# Vehicle_Accident_Detection.net
KiCad netlist of a schematic drawn in EasyEDA
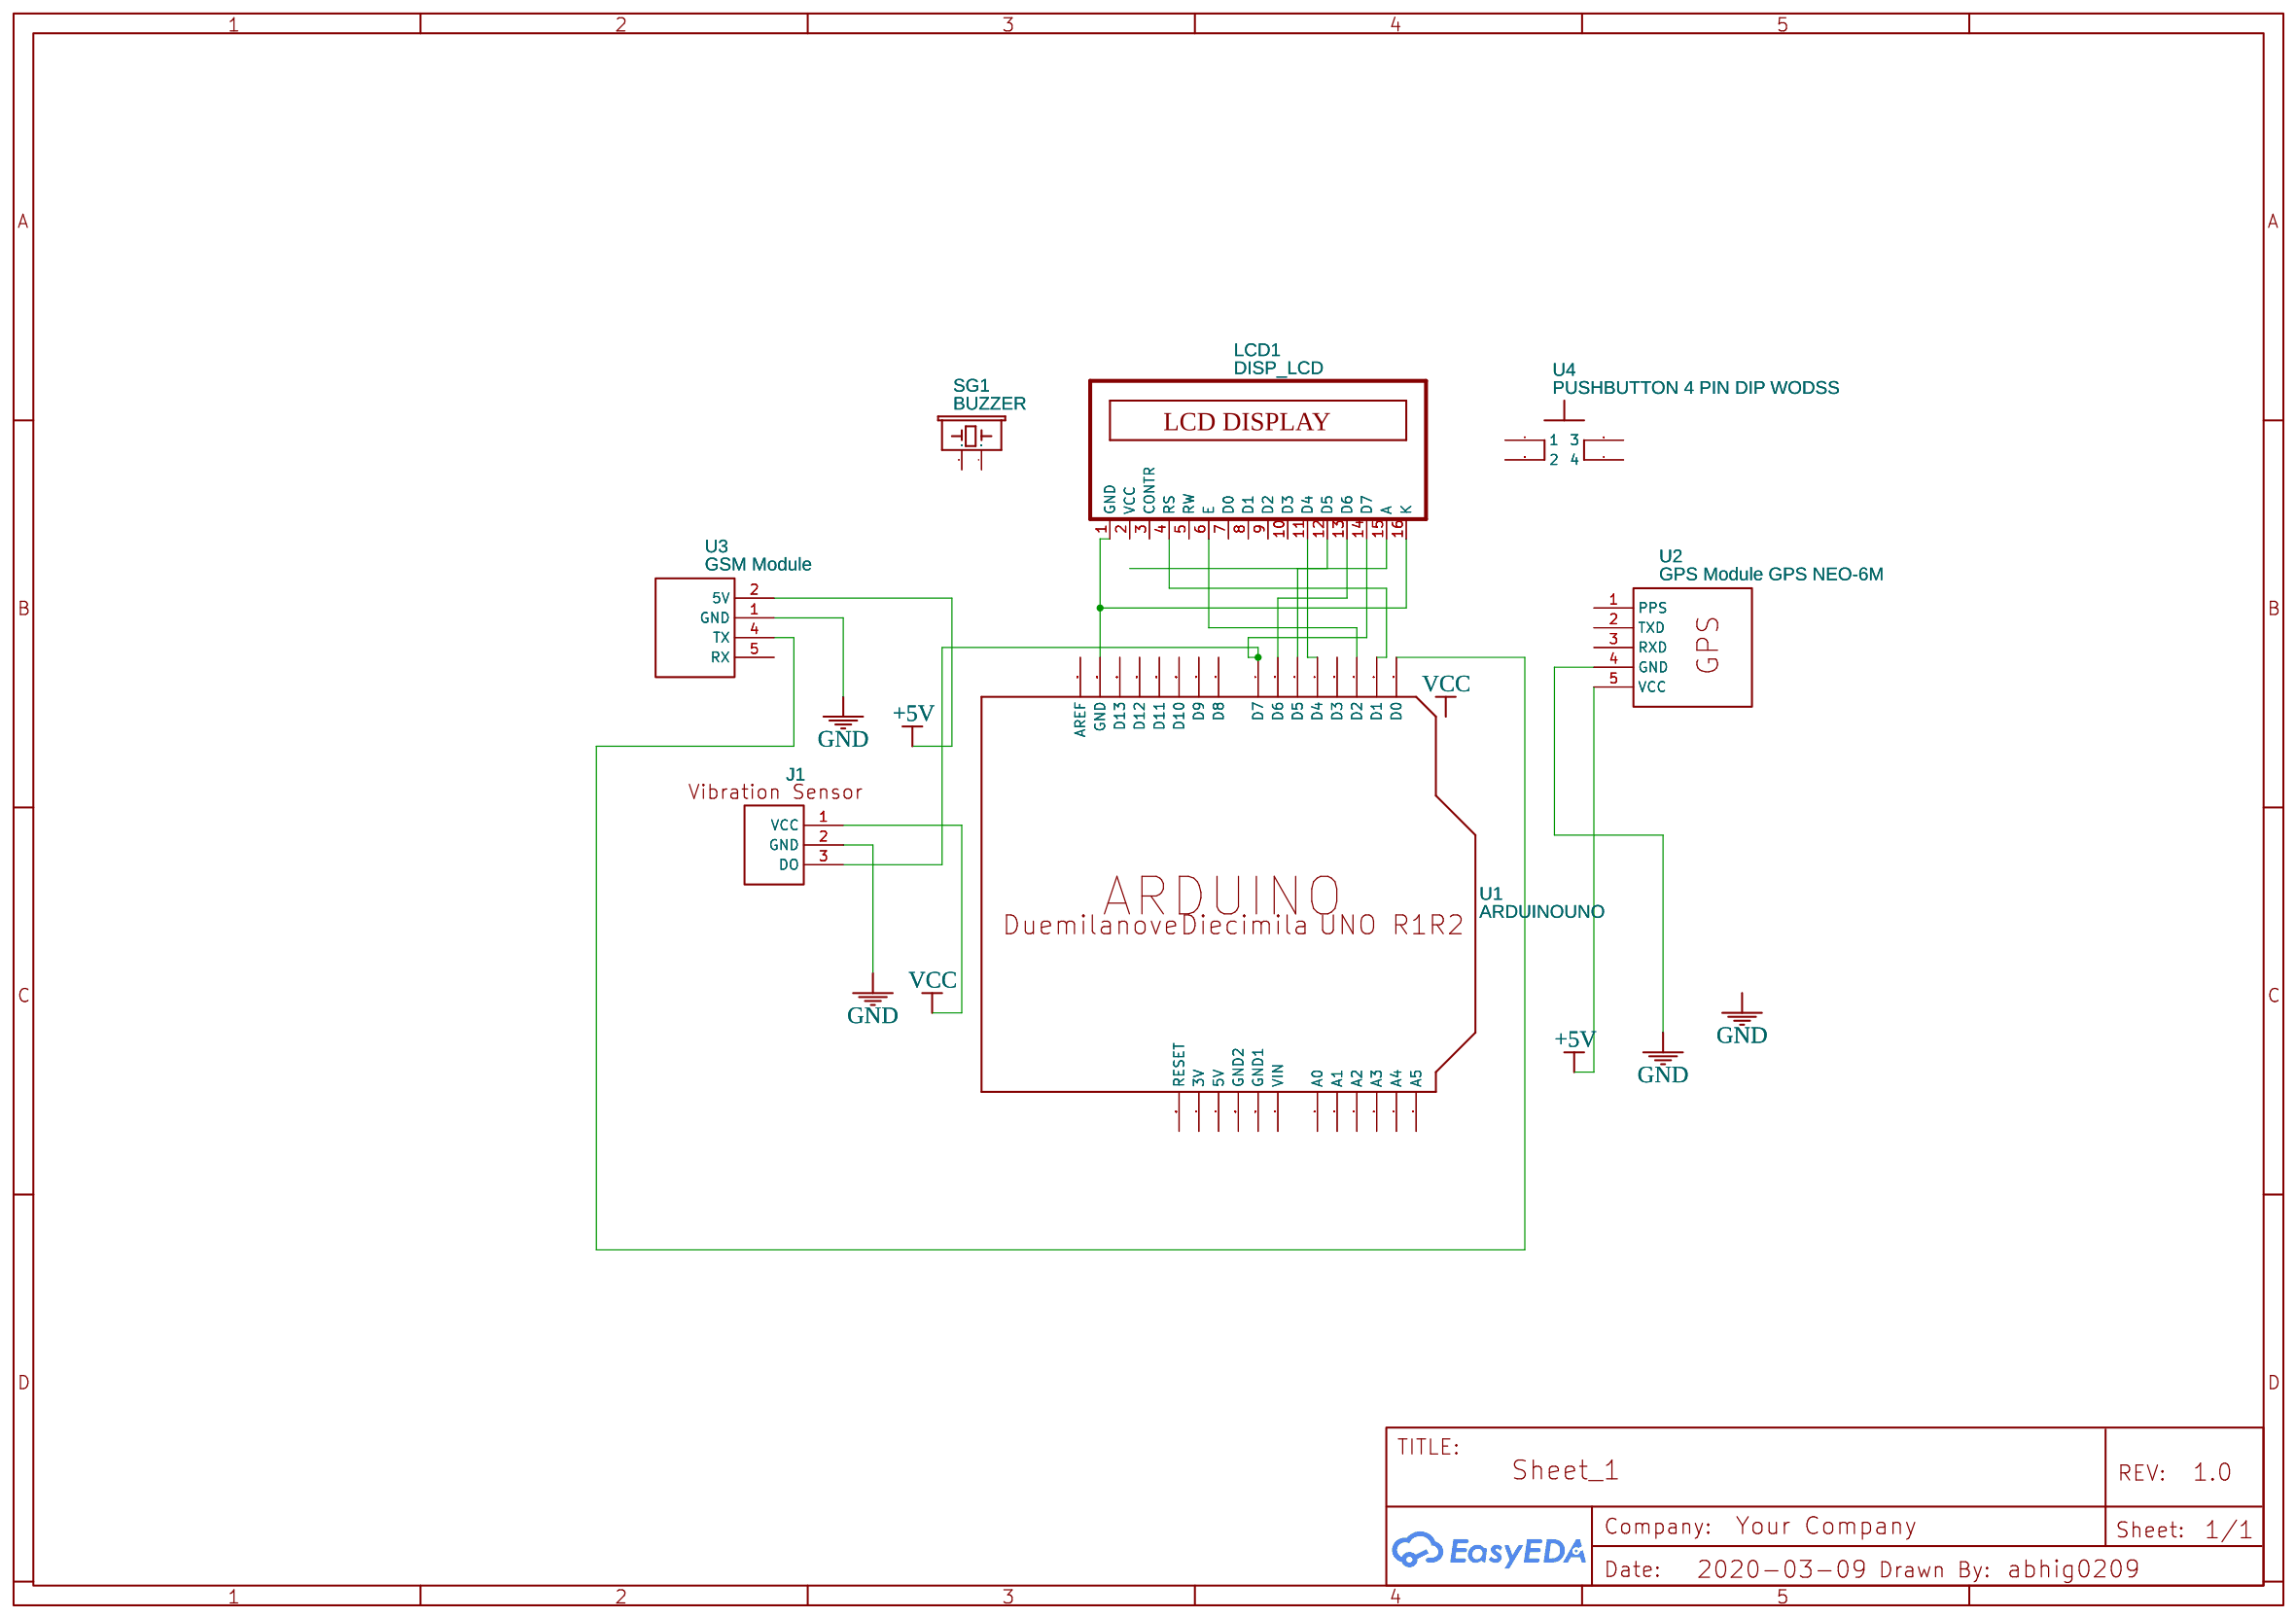
[diagram p0: schematic sheet]

(export (version "E")
  (design (tool "Eeschema 10.0.6"))
  (components
    (comp (ref "J1")
      (value "Vibration_Sensor")
      (fields (field (name "BOM_Manufacturer Part") "Vibration Sensor"))
      (libsource (lib "") (part "Vibration_Sensor"))
    )
    (comp (ref "LCD1") (value "DISP_LCD") (libsource (lib "") (part "DISP_LCD")))
    (comp (ref "SG1") (value "BUZZER") (libsource (lib "") (part "BUZZER")))
    (comp (ref "U1") (value "ARDUINOUNO") (libsource (lib "") (part "ARDUINOUNO")))
    (comp (ref "U2") (value "GPS Module GPS NEO-6M") (libsource (lib "") (part "GPS Module GPS NEO-6M")))
    (comp (ref "U3") (value "GSM Module") (libsource (lib "") (part "GSM Module")))
    (comp (ref "U4")
      (value "PUSHBUTTON 4 PIN DIP WODSS")
      (fields (field (name "BOM_Manufacturer Part") "Pushbutton"))
      (libsource (lib "") (part "PUSHBUTTON 4 PIN DIP WODSS"))
    )
  )
  (nets
    (net (code "1") (name "+5V") (class "Default")
      (node (ref "U2") (pin "5") (pinfunction "VCC_5") (pintype "unspecified"))
      (node (ref "U3") (pin "2") (pinfunction "5V_2") (pintype "unspecified"))
    )
    (net (code "2") (name "GND") (class "Default")
      (node (ref "J1") (pin "2") (pinfunction "GND_2") (pintype "unspecified"))
      (node (ref "U2") (pin "4") (pinfunction "GND_4") (pintype "unspecified"))
      (node (ref "U3") (pin "1") (pinfunction "GND_1") (pintype "unspecified"))
    )
    (net (code "3") (name "Net-(J1-DO)") (class "Default")
      (node (ref "J1") (pin "3") (pinfunction "DO_3") (pintype "unspecified"))
      (node (ref "LCD1") (pin "14") (pinfunction "D7_14") (pintype "input"))
      (node (ref "U1") (pin "D7") (pinfunction "D7_D7") (pintype "unspecified"))
    )
    (net (code "4") (name "Net-(LCD1-D4)") (class "Default")
      (node (ref "LCD1") (pin "11") (pinfunction "D4_11") (pintype "input"))
      (node (ref "U1") (pin "D4") (pinfunction "D4_D4") (pintype "unspecified"))
    )
    (net (code "5") (name "Net-(LCD1-D5)") (class "Default")
      (node (ref "LCD1") (pin "12") (pinfunction "D5_12") (pintype "input"))
      (node (ref "U1") (pin "D5") (pinfunction "D5_D5") (pintype "unspecified"))
    )
    (net (code "6") (name "Net-(LCD1-D6)") (class "Default")
      (node (ref "LCD1") (pin "13") (pinfunction "D6_13") (pintype "input"))
      (node (ref "U1") (pin "D6") (pinfunction "D6_D6") (pintype "unspecified"))
    )
    (net (code "7") (name "Net-(LCD1-E)") (class "Default")
      (node (ref "LCD1") (pin "6") (pinfunction "E_6") (pintype "input"))
      (node (ref "U1") (pin "D2") (pinfunction "D2_D2") (pintype "unspecified"))
    )
    (net (code "8") (name "Net-(LCD1-GND)") (class "Default")
      (node (ref "LCD1") (pin "1") (pinfunction "GND_1") (pintype "unspecified"))
      (node (ref "LCD1") (pin "16") (pinfunction "K_16") (pintype "unspecified"))
      (node (ref "U1") (pin "GND") (pinfunction "GND_GND") (pintype "passive"))
    )
    (net (code "9") (name "Net-(LCD1-RS)") (class "Default")
      (node (ref "LCD1") (pin "4") (pinfunction "RS_4") (pintype "input"))
      (node (ref "U1") (pin "D1") (pinfunction "D1_D1") (pintype "unspecified"))
    )
    (net (code "10") (name "Net-(U3-TX)") (class "Default")
      (node (ref "U1") (pin "D0") (pinfunction "D0_D0") (pintype "unspecified"))
      (node (ref "U3") (pin "4") (pinfunction "TX_4") (pintype "unspecified"))
    )
    (net (code "11") (name "VCC") (class "Default")
      (node (ref "J1") (pin "1") (pinfunction "VCC_1") (pintype "unspecified"))
    )
    (net (code "12") (name "unconnected-(LCD1-A-Pad15)") (class "Default")
      (node (ref "LCD1") (pin "15") (pinfunction "A_15") (pintype "unspecified"))
    )
    (net (code "13") (name "unconnected-(LCD1-CONTR-Pad3)") (class "Default")
      (node (ref "LCD1") (pin "3") (pinfunction "CONTR_3") (pintype "input"))
    )
    (net (code "14") (name "unconnected-(LCD1-D0-Pad7)") (class "Default")
      (node (ref "LCD1") (pin "7") (pinfunction "D0_7") (pintype "input"))
    )
    (net (code "15") (name "unconnected-(LCD1-D1-Pad8)") (class "Default")
      (node (ref "LCD1") (pin "8") (pinfunction "D1_8") (pintype "input"))
    )
    (net (code "16") (name "unconnected-(LCD1-D2-Pad9)") (class "Default")
      (node (ref "LCD1") (pin "9") (pinfunction "D2_9") (pintype "input"))
    )
    (net (code "17") (name "unconnected-(LCD1-D3-Pad10)") (class "Default")
      (node (ref "LCD1") (pin "10") (pinfunction "D3_10") (pintype "input"))
    )
    (net (code "18") (name "unconnected-(LCD1-RW-Pad5)") (class "Default")
      (node (ref "LCD1") (pin "5") (pinfunction "RW_5") (pintype "input"))
    )
    (net (code "19") (name "unconnected-(LCD1-VCC-Pad2)") (class "Default")
      (node (ref "LCD1") (pin "2") (pinfunction "VCC_2") (pintype "unspecified"))
    )
    (net (code "20") (name "unconnected-(SG1-1-Pad+)") (class "Default")
      (node (ref "SG1") (pin "+") (pinfunction "1_+") (pintype "unspecified"))
    )
    (net (code "21") (name "unconnected-(SG1-2-Pad-)") (class "Default")
      (node (ref "SG1") (pin "-") (pinfunction "2_-") (pintype "unspecified"))
    )
    (net (code "22") (name "unconnected-(U1-Pad3V)") (class "Default")
      (node (ref "U1") (pin "3V") (pinfunction "3V_3V") (pintype "passive"))
    )
    (net (code "23") (name "unconnected-(U1-Pad5V)") (class "Default")
      (node (ref "U1") (pin "5V") (pinfunction "5V_5V") (pintype "passive"))
    )
    (net (code "24") (name "unconnected-(U1-PadA0)") (class "Default")
      (node (ref "U1") (pin "A0") (pinfunction "A0_A0") (pintype "unspecified"))
    )
    (net (code "25") (name "unconnected-(U1-PadA1)") (class "Default")
      (node (ref "U1") (pin "A1") (pinfunction "A1_A1") (pintype "unspecified"))
    )
    (net (code "26") (name "unconnected-(U1-PadA2)") (class "Default")
      (node (ref "U1") (pin "A2") (pinfunction "A2_A2") (pintype "unspecified"))
    )
    (net (code "27") (name "unconnected-(U1-PadA3)") (class "Default")
      (node (ref "U1") (pin "A3") (pinfunction "A3_A3") (pintype "unspecified"))
    )
    (net (code "28") (name "unconnected-(U1-PadA4)") (class "Default")
      (node (ref "U1") (pin "A4") (pinfunction "A4_A4") (pintype "unspecified"))
    )
    (net (code "29") (name "unconnected-(U1-PadA5)") (class "Default")
      (node (ref "U1") (pin "A5") (pinfunction "A5_A5") (pintype "unspecified"))
    )
    (net (code "30") (name "unconnected-(U1-PadAREF)") (class "Default")
      (node (ref "U1") (pin "AREF") (pinfunction "AREF_AREF") (pintype "unspecified"))
    )
    (net (code "31") (name "unconnected-(U1-PadD3)") (class "Default")
      (node (ref "U1") (pin "D3") (pinfunction "D3_D3") (pintype "unspecified"))
    )
    (net (code "32") (name "unconnected-(U1-PadD8)") (class "Default")
      (node (ref "U1") (pin "D8") (pinfunction "D8_D8") (pintype "unspecified"))
    )
    (net (code "33") (name "unconnected-(U1-PadD9)") (class "Default")
      (node (ref "U1") (pin "D9") (pinfunction "D9_D9") (pintype "unspecified"))
    )
    (net (code "34") (name "unconnected-(U1-PadD10)") (class "Default")
      (node (ref "U1") (pin "D10") (pinfunction "D10_D10") (pintype "unspecified"))
    )
    (net (code "35") (name "unconnected-(U1-PadD11)") (class "Default")
      (node (ref "U1") (pin "D11") (pinfunction "D11_D11") (pintype "unspecified"))
    )
    (net (code "36") (name "unconnected-(U1-PadD12)") (class "Default")
      (node (ref "U1") (pin "D12") (pinfunction "D12_D12") (pintype "unspecified"))
    )
    (net (code "37") (name "unconnected-(U1-PadD13)") (class "Default")
      (node (ref "U1") (pin "D13") (pinfunction "D13_D13") (pintype "unspecified"))
    )
    (net (code "38") (name "unconnected-(U1-PadGND1)") (class "Default")
      (node (ref "U1") (pin "GND1") (pinfunction "GND1_GND1") (pintype "passive"))
    )
    (net (code "39") (name "unconnected-(U1-PadGND2)") (class "Default")
      (node (ref "U1") (pin "GND2") (pinfunction "GND2_GND2") (pintype "passive"))
    )
    (net (code "40") (name "unconnected-(U1-PadRESET)") (class "Default")
      (node (ref "U1") (pin "RESET") (pinfunction "RESET_RESET") (pintype "unspecified"))
    )
    (net (code "41") (name "unconnected-(U1-PadVIN)") (class "Default")
      (node (ref "U1") (pin "VIN") (pinfunction "VIN_VIN") (pintype "passive"))
    )
    (net (code "42") (name "unconnected-(U2-PPS-Pad1)") (class "Default")
      (node (ref "U2") (pin "1") (pinfunction "PPS_1") (pintype "unspecified"))
    )
    (net (code "43") (name "unconnected-(U2-RXD-Pad3)") (class "Default")
      (node (ref "U2") (pin "3") (pinfunction "RXD_3") (pintype "unspecified"))
    )
    (net (code "44") (name "unconnected-(U2-TXD-Pad2)") (class "Default")
      (node (ref "U2") (pin "2") (pinfunction "TXD_2") (pintype "unspecified"))
    )
    (net (code "45") (name "unconnected-(U3-RX-Pad5)") (class "Default")
      (node (ref "U3") (pin "5") (pinfunction "RX_5") (pintype "unspecified"))
    )
    (net (code "46") (name "unconnected-(U4-Pad1)") (class "Default")
      (node (ref "U4") (pin "1") (pinfunction "1_1") (pintype "unspecified"))
    )
    (net (code "47") (name "unconnected-(U4-Pad2)") (class "Default")
      (node (ref "U4") (pin "2") (pinfunction "2_2") (pintype "unspecified"))
    )
    (net (code "48") (name "unconnected-(U4-Pad3)") (class "Default")
      (node (ref "U4") (pin "3") (pinfunction "3_3") (pintype "unspecified"))
    )
    (net (code "49") (name "unconnected-(U4-Pad4)") (class "Default")
      (node (ref "U4") (pin "4") (pinfunction "4_4") (pintype "unspecified"))
    )
  )
)
